# Controlador_de_velocidad_-_Placa_superio.net
KiCad netlist of a schematic drawn in Altium Designer
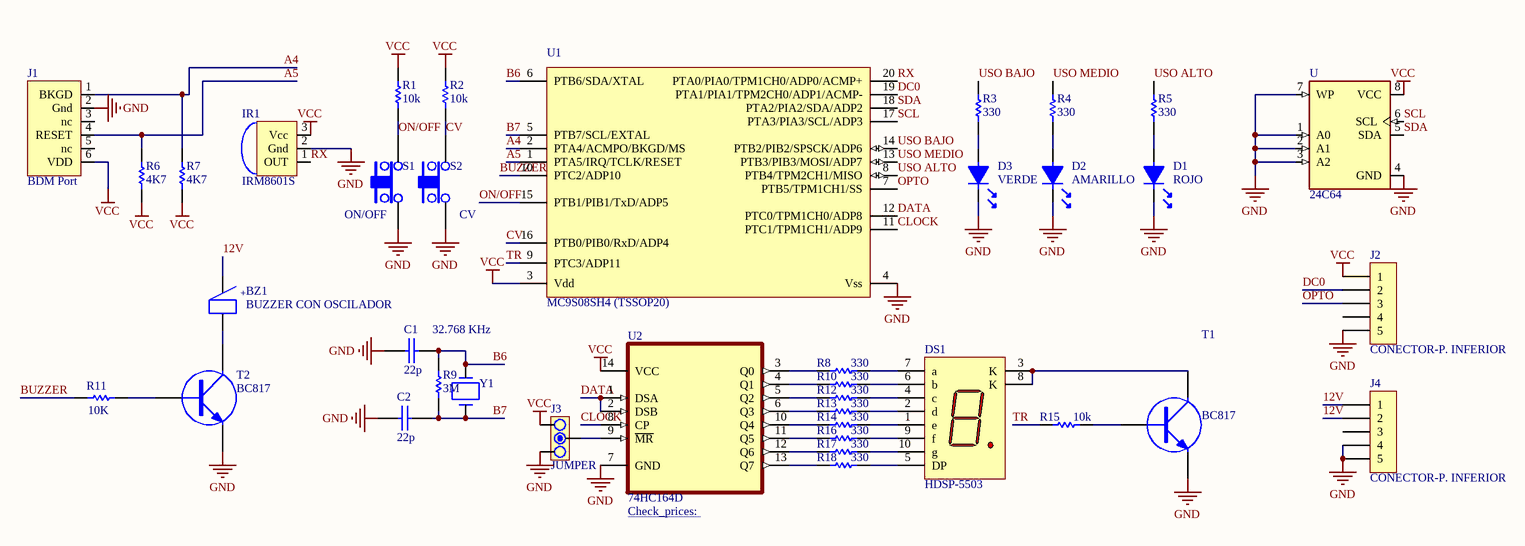
[diagram p0: Controlador de velocidad - Placa superior.SchDoc]

(export (version "E")
  (design (tool "Eeschema 10.0.6"))
  (components
    (comp (ref "BZ1")
      (value "BUZZER CON OSCILADOR")
      (footprint "BUZZER 12MM")
      (libsource (lib "LIBEBAL") (part "BUZZER"))
    )
    (comp (ref "C1") (value "22p") (footprint "0805") (libsource (lib "LIBPIOIX") (part "CAP")))
    (comp (ref "C2") (value "22p") (footprint "0805") (libsource (lib "LIBPIOIX") (part "CAP")))
    (comp (ref "D1") (value "ROJO") (footprint "LED5") (libsource (lib "LIBPIOIX") (part "LED")))
    (comp (ref "D2") (value "AMARILLO") (footprint "LED5") (libsource (lib "LIBPIOIX") (part "LED")))
    (comp (ref "D3") (value "VERDE") (footprint "LED5") (libsource (lib "LIBPIOIX") (part "LED")))
    (comp (ref "DS1")
      (value "HDSP-5503")
      (footprint "H-10")
      (description "14.22 mm Gray Surface HER 7-Segment Display: CC, RH DP")
      (fields (field (name "PUBLISHER") "Altium Limited"))
      (libsource (lib "Agilent LED Display 7-Segment, 1-Digit") (part "HDSP-5503"))
    )
    (comp (ref "IR1")
      (value "IRM8601S")
      (footprint "IRM8601S")
      (description "Sensor IR")
      (libsource (lib "*") (part "IRM8601S"))
    )
    (comp (ref "J1") (value "BDM Port") (footprint "JBDM") (libsource (lib "*") (part "JBDM")))
    (comp (ref "J2")
      (value "CONECTOR-P. INFERIOR")
      (footprint "SIP5")
      (libsource (lib "LIBEBAL") (part "CON5"))
    )
    (comp (ref "J3") (value "JUMPER") (footprint "JUMPER3") (libsource (lib "LIBPIOIX") (part "JUMPER3")))
    (comp (ref "J4")
      (value "CONECTOR-P. INFERIOR")
      (footprint "SIP5")
      (libsource (lib "LIBEBAL") (part "CON5"))
    )
    (comp (ref "R1") (value "10k") (footprint "0805") (libsource (lib "LIBPIOIX") (part "RES")))
    (comp (ref "R2") (value "10k") (footprint "0805") (libsource (lib "LIBPIOIX") (part "RES")))
    (comp (ref "R3") (value "330") (footprint "0805") (libsource (lib "LIBPIOIX") (part "RES")))
    (comp (ref "R4") (value "330") (footprint "0805") (libsource (lib "LIBPIOIX") (part "RES")))
    (comp (ref "R5") (value "330") (footprint "0805") (libsource (lib "LIBPIOIX") (part "RES")))
    (comp (ref "R6") (value "4K7") (footprint "0805") (libsource (lib "LIBPIOIX") (part "RES")))
    (comp (ref "R7") (value "4K7") (footprint "0805") (libsource (lib "LIBPIOIX") (part "RES")))
    (comp (ref "R8") (value "330") (footprint "0805") (libsource (lib "LIB PIO IX") (part "RES")))
    (comp (ref "R9") (value "3M") (footprint "0805") (libsource (lib "LIB PIO IX") (part "RES")))
    (comp (ref "R10") (value "330") (footprint "0805") (libsource (lib "LIB PIO IX") (part "RES")))
    (comp (ref "R11") (value "10K") (footprint "0805") (libsource (lib "LIBPIOIX") (part "RES")))
    (comp (ref "R12") (value "330") (footprint "0805") (libsource (lib "LIB PIO IX") (part "RES")))
    (comp (ref "R13") (value "330") (footprint "0805") (libsource (lib "LIB PIO IX") (part "RES")))
    (comp (ref "R14") (value "330") (footprint "0805") (libsource (lib "LIB PIO IX") (part "RES")))
    (comp (ref "R15") (value "10k") (footprint "0805") (libsource (lib "LIB PIO IX") (part "RES")))
    (comp (ref "R16") (value "330") (footprint "0805") (libsource (lib "LIB PIO IX") (part "RES")))
    (comp (ref "R17") (value "330") (footprint "0805") (libsource (lib "LIB PIO IX") (part "RES")))
    (comp (ref "R18") (value "330") (footprint "0805") (libsource (lib "LIB PIO IX") (part "RES")))
    (comp (ref "S1")
      (value "ON/OFF")
      (footprint "TACTSWITCH")
      (libsource (lib "LIBPIOIX") (part "TACT SWITCH"))
    )
    (comp (ref "S2") (value "CV") (footprint "TACTSWITCH") (libsource (lib "LIBPIOIX") (part "TACT SWITCH")))
    (comp (ref "T1") (value "BC817") (footprint "SOT23") (libsource (lib "LIBPIOIX") (part "TRANSISTOR NPN")))
    (comp (ref "T2") (value "BC817") (footprint "SOT23") (libsource (lib "LIBPIOIX") (part "TRANSISTOR NPN")))
    (comp (ref "U")
      (value "24C64")
      (footprint "SOIC127P600X175-8N")
      (description "EEPROM Memory IC 256Kb _32K x 8_ I²C 1MHz 550ns 8-SOIC")
      (fields
        (field (name "MP") "AT24C256C-SSHL-T")
        (field (name "DIGI-KEY_PART_NUMBER") "AT24C256C-SSHL-TCT-ND")
      )
      (libsource (lib "AT24C256C-SSHL-T") (part "AT24C256C-SSHL-T"))
    )
    (comp (ref "U1")
      (value "MC9S08SH4 (TSSOP20)")
      (footprint "TSSOP20")
      (libsource (lib "*") (part "MC9S08SH8_20"))
    )
    (comp (ref "U2")
      (value "74HC164D")
      (footprint "SOIC127P600X175-14N")
      (description "Shift Shift Register 1 Element 8 Bit 14-SO")
      (fields (field (name "MF") "Nexperia USA") (field (name "MP") "74HC164D,653"))
      (libsource (lib "74HC164D_653") (part "74HC164D,653"))
    )
    (comp (ref "Y1") (value "32.768 KHz") (footprint "X32768") (libsource (lib "*") (part "CRYSTAL")))
  )
  (nets
    (net (code "1") (name "/12V") (class "Default")
      (node (ref "BZ1") (pin "1") (pinfunction "1_1") (pintype "passive"))
      (node (ref "J4") (pin "1") (pinfunction "1_1") (pintype "passive"))
      (node (ref "J4") (pin "2") (pinfunction "2_2") (pintype "passive"))
    )
    (net (code "2") (name "/A4") (class "Default")
      (node (ref "J1") (pin "1") (pinfunction "BKGD_1") (pintype "passive"))
      (node (ref "R7") (pin "2") (pinfunction "2_2") (pintype "passive"))
      (node (ref "U1") (pin "2") (pinfunction "PTA4/ACMPO/BKGD/MS_2") (pintype "passive"))
    )
    (net (code "3") (name "/A5") (class "Default")
      (node (ref "J1") (pin "4") (pinfunction "RESET_4") (pintype "passive"))
      (node (ref "R6") (pin "2") (pinfunction "2_2") (pintype "passive"))
      (node (ref "U1") (pin "1") (pinfunction "PTA5/IRQ/TCLK/RESET_1") (pintype "passive"))
    )
    (net (code "4") (name "/B6") (class "Default")
      (node (ref "C1") (pin "1") (pinfunction "1_1") (pintype "passive"))
      (node (ref "R9") (pin "2") (pinfunction "2_2") (pintype "passive"))
      (node (ref "U1") (pin "6") (pinfunction "PTB6/SDA/XTAL_6") (pintype "passive"))
      (node (ref "Y1") (pin "2") (pinfunction "2_2") (pintype "passive"))
    )
    (net (code "5") (name "/B7") (class "Default")
      (node (ref "C2") (pin "1") (pinfunction "1_1") (pintype "passive"))
      (node (ref "R9") (pin "1") (pinfunction "1_1") (pintype "passive"))
      (node (ref "U1") (pin "5") (pinfunction "PTB7/SCL/EXTAL_5") (pintype "passive"))
      (node (ref "Y1") (pin "1") (pinfunction "1_1") (pintype "passive"))
    )
    (net (code "6") (name "/BUZZER") (class "Default")
      (node (ref "R11") (pin "1") (pinfunction "1_1") (pintype "passive"))
      (node (ref "U1") (pin "10") (pinfunction "PTC2/ADP10_10") (pintype "passive"))
    )
    (net (code "7") (name "/CLOCK") (class "Default")
      (node (ref "U1") (pin "11") (pinfunction "PTC1/TPM1CH1/ADP9_11") (pintype "passive"))
      (node (ref "U2") (pin "8") (pinfunction "CP_8") (pintype "input"))
    )
    (net (code "8") (name "/CV") (class "Default")
      (node (ref "R2") (pin "1") (pinfunction "1_1") (pintype "passive"))
      (node (ref "S2") (pin "2") (pinfunction "2_2") (pintype "passive"))
      (node (ref "U1") (pin "16") (pinfunction "PTB0/PIB0/RxD/ADP4_16") (pintype "passive"))
    )
    (net (code "9") (name "/DATA") (class "Default")
      (node (ref "U1") (pin "12") (pinfunction "PTC0/TPM1CH0/ADP8_12") (pintype "passive"))
      (node (ref "U2") (pin "1") (pinfunction "DSA_1") (pintype "input"))
      (node (ref "U2") (pin "2") (pinfunction "DSB_2") (pintype "input"))
    )
    (net (code "10") (name "/DC0") (class "Default")
      (node (ref "J2") (pin "2") (pinfunction "2_2") (pintype "passive"))
      (node (ref "U1") (pin "19") (pinfunction "PTA1/PIA1/TPM2CH0/ADP1/ACMP-_19") (pintype "passive"))
    )
    (net (code "11") (name "/ON{slash}OFF") (class "Default")
      (node (ref "R1") (pin "1") (pinfunction "1_1") (pintype "passive"))
      (node (ref "S1") (pin "2") (pinfunction "2_2") (pintype "passive"))
      (node (ref "U1") (pin "15") (pinfunction "PTB1/PIB1/TxD/ADP5_15") (pintype "passive"))
    )
    (net (code "12") (name "/OPTO") (class "Default")
      (node (ref "J2") (pin "3") (pinfunction "3_3") (pintype "passive"))
      (node (ref "U1") (pin "7") (pinfunction "PTB5/TPM1CH1/SS_7") (pintype "passive"))
    )
    (net (code "13") (name "/RX") (class "Default")
      (node (ref "IR1") (pin "1") (pinfunction "OUT_1") (pintype "passive"))
      (node (ref "U1") (pin "20") (pinfunction "PTA0/PIA0/TPM1CH0/ADP0/ACMP+_20") (pintype "passive"))
    )
    (net (code "14") (name "/SCL") (class "Default")
      (node (ref "U") (pin "6") (pinfunction "SCL_6") (pintype "input"))
      (node (ref "U1") (pin "17") (pinfunction "PTA3/PIA3/SCL/ADP3_17") (pintype "passive"))
    )
    (net (code "15") (name "/SDA") (class "Default")
      (node (ref "U") (pin "5") (pinfunction "SDA_5") (pintype "bidirectional"))
      (node (ref "U1") (pin "18") (pinfunction "PTA2/PIA2/SDA/ADP2_18") (pintype "passive"))
    )
    (net (code "16") (name "/TR") (class "Default")
      (node (ref "R15") (pin "1") (pinfunction "1_1") (pintype "passive"))
      (node (ref "U1") (pin "9") (pinfunction "PTC3/ADP11_9") (pintype "passive"))
    )
    (net (code "17") (name "/USO ALTO") (class "Default")
      (node (ref "R5") (pin "2") (pinfunction "2_2") (pintype "passive"))
      (node (ref "U1") (pin "8") (pinfunction "PTB4/TPM2CH1/MISO_8") (pintype "bidirectional"))
    )
    (net (code "18") (name "/USO BAJO") (class "Default")
      (node (ref "R3") (pin "2") (pinfunction "2_2") (pintype "passive"))
      (node (ref "U1") (pin "14") (pinfunction "PTB2/PIB2/SPSCK/ADP6_14") (pintype "bidirectional"))
    )
    (net (code "19") (name "/USO MEDIO") (class "Default")
      (node (ref "R4") (pin "2") (pinfunction "2_2") (pintype "passive"))
      (node (ref "U1") (pin "13") (pinfunction "PTB3/PIB3/MOSI/ADP7_13") (pintype "bidirectional"))
    )
    (net (code "20") (name "GND") (class "Default")
      (node (ref "C1") (pin "2") (pinfunction "2_2") (pintype "passive"))
      (node (ref "C2") (pin "2") (pinfunction "2_2") (pintype "passive"))
      (node (ref "D1") (pin "2") (pinfunction "2_2") (pintype "passive"))
      (node (ref "D2") (pin "2") (pinfunction "2_2") (pintype "passive"))
      (node (ref "D3") (pin "2") (pinfunction "2_2") (pintype "passive"))
      (node (ref "IR1") (pin "2") (pinfunction "Gnd_2") (pintype "passive"))
      (node (ref "J1") (pin "2") (pinfunction "Gnd_2") (pintype "passive"))
      (node (ref "J2") (pin "5") (pinfunction "5_5") (pintype "passive"))
      (node (ref "J3") (pin "1") (pinfunction "1_1") (pintype "passive"))
      (node (ref "J4") (pin "4") (pinfunction "4_4") (pintype "passive"))
      (node (ref "J4") (pin "5") (pinfunction "5_5") (pintype "passive"))
      (node (ref "S1") (pin "1") (pinfunction "1_1") (pintype "passive"))
      (node (ref "S2") (pin "1") (pinfunction "1_1") (pintype "passive"))
      (node (ref "T1") (pin "3") (pinfunction "E_3") (pintype "passive"))
      (node (ref "T2") (pin "3") (pinfunction "E_3") (pintype "passive"))
      (node (ref "U") (pin "1") (pinfunction "A0_1") (pintype "input"))
      (node (ref "U") (pin "2") (pinfunction "A1_2") (pintype "input"))
      (node (ref "U") (pin "3") (pinfunction "A2_3") (pintype "input"))
      (node (ref "U") (pin "4") (pinfunction "GND_4") (pintype "power_in"))
      (node (ref "U") (pin "7") (pinfunction "WP_7") (pintype "input"))
      (node (ref "U1") (pin "4") (pinfunction "Vss_4") (pintype "passive"))
      (node (ref "U2") (pin "7") (pinfunction "GND_7") (pintype "passive"))
    )
    (net (code "21") (name "Net-(D1-Pad1)") (class "Default")
      (node (ref "D1") (pin "1") (pinfunction "1_1") (pintype "passive"))
      (node (ref "R5") (pin "1") (pinfunction "1_1") (pintype "passive"))
    )
    (net (code "22") (name "Net-(D2-Pad1)") (class "Default")
      (node (ref "D2") (pin "1") (pinfunction "1_1") (pintype "passive"))
      (node (ref "R4") (pin "1") (pinfunction "1_1") (pintype "passive"))
    )
    (net (code "23") (name "Net-(D3-Pad1)") (class "Default")
      (node (ref "D3") (pin "1") (pinfunction "1_1") (pintype "passive"))
      (node (ref "R3") (pin "1") (pinfunction "1_1") (pintype "passive"))
    )
    (net (code "24") (name "Net-(DS1-DP)") (class "Default")
      (node (ref "DS1") (pin "5") (pinfunction "DP_5") (pintype "passive"))
      (node (ref "R18") (pin "2") (pinfunction "2_2") (pintype "passive"))
    )
    (net (code "25") (name "Net-(DS1-a)") (class "Default")
      (node (ref "DS1") (pin "7") (pinfunction "a_7") (pintype "passive"))
      (node (ref "R8") (pin "2") (pinfunction "2_2") (pintype "passive"))
    )
    (net (code "26") (name "Net-(DS1-b)") (class "Default")
      (node (ref "DS1") (pin "6") (pinfunction "b_6") (pintype "passive"))
      (node (ref "R10") (pin "2") (pinfunction "2_2") (pintype "passive"))
    )
    (net (code "27") (name "Net-(DS1-c)") (class "Default")
      (node (ref "DS1") (pin "4") (pinfunction "c_4") (pintype "passive"))
      (node (ref "R12") (pin "2") (pinfunction "2_2") (pintype "passive"))
    )
    (net (code "28") (name "Net-(DS1-d)") (class "Default")
      (node (ref "DS1") (pin "2") (pinfunction "d_2") (pintype "passive"))
      (node (ref "R13") (pin "2") (pinfunction "2_2") (pintype "passive"))
    )
    (net (code "29") (name "Net-(DS1-e)") (class "Default")
      (node (ref "DS1") (pin "1") (pinfunction "e_1") (pintype "passive"))
      (node (ref "R14") (pin "2") (pinfunction "2_2") (pintype "passive"))
    )
    (net (code "30") (name "Net-(DS1-f)") (class "Default")
      (node (ref "DS1") (pin "9") (pinfunction "f_9") (pintype "passive"))
      (node (ref "R16") (pin "2") (pinfunction "2_2") (pintype "passive"))
    )
    (net (code "31") (name "Net-(DS1-g)") (class "Default")
      (node (ref "DS1") (pin "10") (pinfunction "g_10") (pintype "passive"))
      (node (ref "R17") (pin "2") (pinfunction "2_2") (pintype "passive"))
    )
    (net (code "32") (name "Net-(T1-B)") (class "Default")
      (node (ref "R15") (pin "2") (pinfunction "2_2") (pintype "passive"))
      (node (ref "T1") (pin "1") (pinfunction "B_1") (pintype "passive"))
    )
    (net (code "33") (name "Net-(T1-C)") (class "Default")
      (node (ref "DS1") (pin "3") (pinfunction "K_3") (pintype "passive"))
      (node (ref "DS1") (pin "8") (pinfunction "K_8") (pintype "passive"))
      (node (ref "T1") (pin "2") (pinfunction "C_2") (pintype "passive"))
    )
    (net (code "34") (name "Net-(T2-B)") (class "Default")
      (node (ref "R11") (pin "2") (pinfunction "2_2") (pintype "passive"))
      (node (ref "T2") (pin "1") (pinfunction "B_1") (pintype "passive"))
    )
    (net (code "35") (name "Net-(T2-C)") (class "Default")
      (node (ref "BZ1") (pin "2") (pinfunction "2_2") (pintype "passive"))
      (node (ref "T2") (pin "2") (pinfunction "C_2") (pintype "passive"))
    )
    (net (code "36") (name "Net-(U2-Q0)") (class "Default")
      (node (ref "R8") (pin "1") (pinfunction "1_1") (pintype "passive"))
      (node (ref "U2") (pin "3") (pinfunction "Q0_3") (pintype "output"))
    )
    (net (code "37") (name "Net-(U2-Q1)") (class "Default")
      (node (ref "R10") (pin "1") (pinfunction "1_1") (pintype "passive"))
      (node (ref "U2") (pin "4") (pinfunction "Q1_4") (pintype "output"))
    )
    (net (code "38") (name "Net-(U2-Q2)") (class "Default")
      (node (ref "R12") (pin "1") (pinfunction "1_1") (pintype "passive"))
      (node (ref "U2") (pin "5") (pinfunction "Q2_5") (pintype "output"))
    )
    (net (code "39") (name "Net-(U2-Q3)") (class "Default")
      (node (ref "R13") (pin "1") (pinfunction "1_1") (pintype "passive"))
      (node (ref "U2") (pin "6") (pinfunction "Q3_6") (pintype "output"))
    )
    (net (code "40") (name "Net-(U2-Q4)") (class "Default")
      (node (ref "R14") (pin "1") (pinfunction "1_1") (pintype "passive"))
      (node (ref "U2") (pin "10") (pinfunction "Q4_10") (pintype "output"))
    )
    (net (code "41") (name "Net-(U2-Q5)") (class "Default")
      (node (ref "R16") (pin "1") (pinfunction "1_1") (pintype "passive"))
      (node (ref "U2") (pin "11") (pinfunction "Q5_11") (pintype "output"))
    )
    (net (code "42") (name "Net-(U2-Q6)") (class "Default")
      (node (ref "R17") (pin "1") (pinfunction "1_1") (pintype "passive"))
      (node (ref "U2") (pin "12") (pinfunction "Q6_12") (pintype "output"))
    )
    (net (code "43") (name "Net-(U2-Q7)") (class "Default")
      (node (ref "R18") (pin "1") (pinfunction "1_1") (pintype "passive"))
      (node (ref "U2") (pin "13") (pinfunction "Q7_13") (pintype "output"))
    )
    (net (code "44") (name "Net-(U2-~{MR})") (class "Default")
      (node (ref "J3") (pin "2") (pinfunction "2_2") (pintype "passive"))
      (node (ref "U2") (pin "9") (pinfunction "~{MR}_9") (pintype "input"))
    )
    (net (code "45") (name "VCC") (class "Default")
      (node (ref "IR1") (pin "3") (pinfunction "Vcc_3") (pintype "passive"))
      (node (ref "J1") (pin "6") (pinfunction "VDD_6") (pintype "passive"))
      (node (ref "J2") (pin "1") (pinfunction "1_1") (pintype "passive"))
      (node (ref "J3") (pin "3") (pinfunction "3_3") (pintype "passive"))
      (node (ref "R1") (pin "2") (pinfunction "2_2") (pintype "passive"))
      (node (ref "R2") (pin "2") (pinfunction "2_2") (pintype "passive"))
      (node (ref "R6") (pin "1") (pinfunction "1_1") (pintype "passive"))
      (node (ref "R7") (pin "1") (pinfunction "1_1") (pintype "passive"))
      (node (ref "U") (pin "8") (pinfunction "VCC_8") (pintype "power_in"))
      (node (ref "U1") (pin "3") (pinfunction "Vdd_3") (pintype "passive"))
      (node (ref "U2") (pin "14") (pinfunction "VCC_14") (pintype "power_in"))
    )
    (net (code "46") (name "unconnected-(J1-nc-Pad3)") (class "Default")
      (node (ref "J1") (pin "3") (pinfunction "nc_3") (pintype "passive"))
    )
    (net (code "47") (name "unconnected-(J1-nc-Pad5)") (class "Default")
      (node (ref "J1") (pin "5") (pinfunction "nc_5") (pintype "passive"))
    )
    (net (code "48") (name "unconnected-(J2-Pad4)") (class "Default")
      (node (ref "J2") (pin "4") (pinfunction "4_4") (pintype "passive"))
    )
    (net (code "49") (name "unconnected-(J4-Pad3)") (class "Default")
      (node (ref "J4") (pin "3") (pinfunction "3_3") (pintype "passive"))
    )
  )
)
